# Amplifier.net
KiCad netlist of a schematic drawn in EAGLE
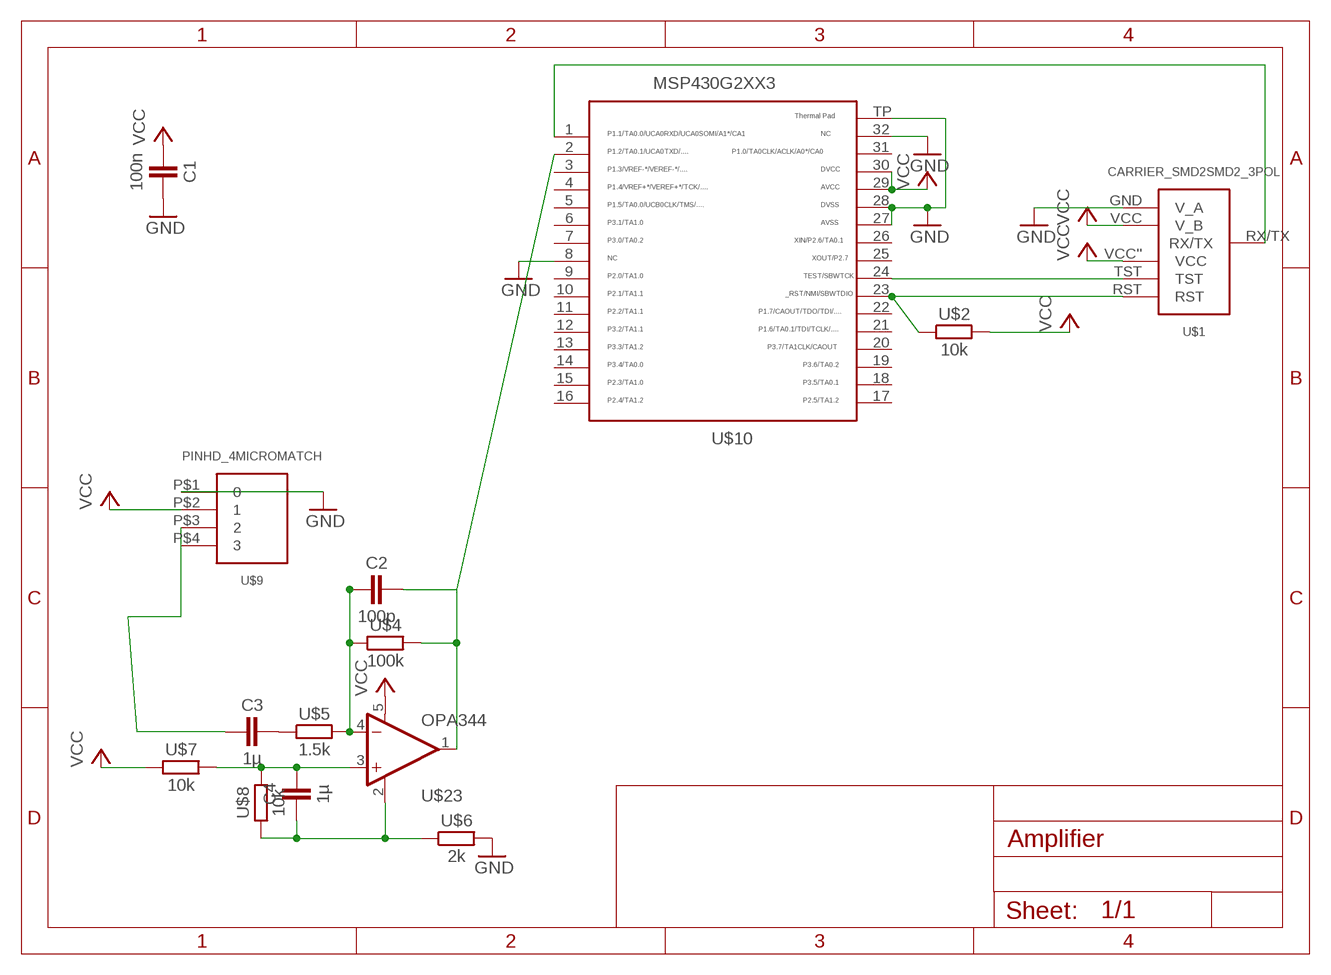
[diagram p0: schematic, sheet 1]

(export (version "E")
  (design (tool "Eeschema 10.0.6"))
  (components
    (comp (ref "C1")
      (value "100n")
      (footprint "eagle-import:603")
      (libsource (lib "eagle-import") (part "CAPACITOR"))
    )
    (comp (ref "C2")
      (value "100p")
      (footprint "eagle-import:603")
      (libsource (lib "eagle-import") (part "CAPACITOR"))
    )
    (comp (ref "C3")
      (value "1µ")
      (footprint "eagle-import:603")
      (libsource (lib "eagle-import") (part "CAPACITOR"))
    )
    (comp (ref "C4")
      (value "1µ")
      (footprint "eagle-import:603")
      (libsource (lib "eagle-import") (part "CAPACITOR"))
    )
    (comp (ref "U$1")
      (value "CARRIER_SMD2SMD2_3POL")
      (footprint "eagle-import:CARRIER_SMD2_3POL")
      (libsource (lib "eagle-import") (part "CARRIER_SMD2SMD2_3POL"))
    )
    (comp (ref "U$2")
      (value "10k")
      (footprint "eagle-import:603")
      (libsource (lib "eagle-import") (part "RESISTOR0603"))
    )
    (comp (ref "U$4")
      (value "100k")
      (footprint "eagle-import:603")
      (libsource (lib "eagle-import") (part "RESISTOR0603"))
    )
    (comp (ref "U$5")
      (value "1.5k")
      (footprint "eagle-import:603")
      (libsource (lib "eagle-import") (part "RESISTOR0603"))
    )
    (comp (ref "U$6")
      (value "2k")
      (footprint "eagle-import:603")
      (libsource (lib "eagle-import") (part "RESISTOR0603"))
    )
    (comp (ref "U$7")
      (value "10k")
      (footprint "eagle-import:603")
      (libsource (lib "eagle-import") (part "RESISTOR0603"))
    )
    (comp (ref "U$8")
      (value "10k")
      (footprint "eagle-import:603")
      (libsource (lib "eagle-import") (part "RESISTOR0603"))
    )
    (comp (ref "U$9")
      (value "PINHD_4MICROMATCH")
      (footprint "eagle-import:MICROMATCH4P0L")
      (libsource (lib "eagle-import") (part "PINHD_4MICROMATCH"))
    )
    (comp (ref "U$10")
      (value "MSP430G2553")
      (footprint "eagle-import:QFN32")
      (libsource (lib "eagle-import") (part "MSP430G2553"))
    )
    (comp (ref "U$23")
      (value "OPA344")
      (footprint "eagle-import:SOT23-5")
      (libsource (lib "eagle-import") (part "OPA344"))
    )
  )
  (nets
    (net (code "1") (name "GND") (class "Default")
      (node (ref "C1") (pin "2") (pinfunction "2_2") (pintype "passive"))
      (node (ref "U$1") (pin "GND") (pinfunction "V_A_GND") (pintype "bidirectional"))
      (node (ref "U$10") (pin "27") (pinfunction "27_27") (pintype "bidirectional"))
      (node (ref "U$10") (pin "28") (pinfunction "28_28") (pintype "bidirectional"))
      (node (ref "U$10") (pin "32") (pinfunction "32_32") (pintype "bidirectional"))
      (node (ref "U$10") (pin "8") (pinfunction "8_8") (pintype "bidirectional"))
      (node (ref "U$10") (pin "TP") (pinfunction "TP_TP") (pintype "bidirectional"))
      (node (ref "U$6") (pin "2") (pinfunction "2_2") (pintype "passive"))
      (node (ref "U$9") (pin "P$1") (pinfunction "0_P$1") (pintype "bidirectional"))
    )
    (net (code "2") (name "Net-(C3-Pad2)") (class "Default")
      (node (ref "C3") (pin "2") (pinfunction "2_2") (pintype "passive"))
      (node (ref "U$5") (pin "1") (pinfunction "1_1") (pintype "passive"))
    )
    (net (code "3") (name "Net-(U$1-PadRST)") (class "Default")
      (node (ref "U$1") (pin "RST") (pinfunction "RST_RST") (pintype "bidirectional"))
      (node (ref "U$10") (pin "23") (pinfunction "23_23") (pintype "bidirectional"))
      (node (ref "U$2") (pin "1") (pinfunction "1_1") (pintype "passive"))
    )
    (net (code "4") (name "Net-(U$1-PadRX{slash}TX)") (class "Default")
      (node (ref "U$1") (pin "RX/TX") (pinfunction "RX/TX_RX/TX") (pintype "bidirectional"))
      (node (ref "U$10") (pin "1") (pinfunction "1_1") (pintype "bidirectional"))
    )
    (net (code "5") (name "Net-(U$1-PadTST)") (class "Default")
      (node (ref "U$1") (pin "TST") (pinfunction "TST_TST") (pintype "bidirectional"))
      (node (ref "U$10") (pin "24") (pinfunction "24_24") (pintype "bidirectional"))
    )
    (net (code "6") (name "Net-(U$9-2)") (class "Default")
      (node (ref "C3") (pin "1") (pinfunction "1_1") (pintype "passive"))
      (node (ref "U$9") (pin "P$3") (pinfunction "2_P$3") (pintype "bidirectional"))
      (node (ref "U$9") (pin "P$4") (pinfunction "3_P$4") (pintype "bidirectional"))
    )
    (net (code "7") (name "Net-(U$23-+IN)") (class "Default")
      (node (ref "C4") (pin "2") (pinfunction "2_2") (pintype "passive"))
      (node (ref "U$23") (pin "3") (pinfunction "+IN_3") (pintype "input"))
      (node (ref "U$7") (pin "2") (pinfunction "2_2") (pintype "passive"))
      (node (ref "U$8") (pin "2") (pinfunction "2_2") (pintype "passive"))
    )
    (net (code "8") (name "Net-(U$23--IN)") (class "Default")
      (node (ref "C2") (pin "1") (pinfunction "1_1") (pintype "passive"))
      (node (ref "U$23") (pin "4") (pinfunction "-IN_4") (pintype "input"))
      (node (ref "U$4") (pin "1") (pinfunction "1_1") (pintype "passive"))
      (node (ref "U$5") (pin "2") (pinfunction "2_2") (pintype "passive"))
    )
    (net (code "9") (name "Net-(U$23-OUT)") (class "Default")
      (node (ref "C2") (pin "2") (pinfunction "2_2") (pintype "passive"))
      (node (ref "U$10") (pin "2") (pinfunction "2_2") (pintype "bidirectional"))
      (node (ref "U$23") (pin "1") (pinfunction "OUT_1") (pintype "output"))
      (node (ref "U$4") (pin "2") (pinfunction "2_2") (pintype "passive"))
    )
    (net (code "10") (name "Net-(U$23-V-)") (class "Default")
      (node (ref "C4") (pin "1") (pinfunction "1_1") (pintype "passive"))
      (node (ref "U$23") (pin "2") (pinfunction "V-_2") (pintype "power_in"))
      (node (ref "U$6") (pin "1") (pinfunction "1_1") (pintype "passive"))
      (node (ref "U$8") (pin "1") (pinfunction "1_1") (pintype "passive"))
    )
    (net (code "11") (name "VCC") (class "Default")
      (node (ref "C1") (pin "1") (pinfunction "1_1") (pintype "passive"))
      (node (ref "U$1") (pin "VCC") (pinfunction "V_B_VCC") (pintype "bidirectional"))
      (node (ref "U$1") (pin "VCC''") (pinfunction "VCC_VCC''") (pintype "bidirectional"))
      (node (ref "U$10") (pin "29") (pinfunction "29_29") (pintype "bidirectional"))
      (node (ref "U$10") (pin "30") (pinfunction "30_30") (pintype "bidirectional"))
      (node (ref "U$2") (pin "2") (pinfunction "2_2") (pintype "passive"))
      (node (ref "U$23") (pin "5") (pinfunction "V+_5") (pintype "power_in"))
      (node (ref "U$7") (pin "1") (pinfunction "1_1") (pintype "passive"))
      (node (ref "U$9") (pin "P$2") (pinfunction "1_P$2") (pintype "bidirectional"))
    )
    (net (code "12") (name "unconnected-(U$10-Pad3)") (class "Default")
      (node (ref "U$10") (pin "3") (pinfunction "3_3") (pintype "bidirectional"))
    )
    (net (code "13") (name "unconnected-(U$10-Pad4)") (class "Default")
      (node (ref "U$10") (pin "4") (pinfunction "4_4") (pintype "bidirectional"))
    )
    (net (code "14") (name "unconnected-(U$10-Pad5)") (class "Default")
      (node (ref "U$10") (pin "5") (pinfunction "5_5") (pintype "bidirectional"))
    )
    (net (code "15") (name "unconnected-(U$10-Pad6)") (class "Default")
      (node (ref "U$10") (pin "6") (pinfunction "6_6") (pintype "bidirectional"))
    )
    (net (code "16") (name "unconnected-(U$10-Pad7)") (class "Default")
      (node (ref "U$10") (pin "7") (pinfunction "7_7") (pintype "bidirectional"))
    )
    (net (code "17") (name "unconnected-(U$10-Pad9)") (class "Default")
      (node (ref "U$10") (pin "9") (pinfunction "9_9") (pintype "bidirectional"))
    )
    (net (code "18") (name "unconnected-(U$10-Pad10)") (class "Default")
      (node (ref "U$10") (pin "10") (pinfunction "10_10") (pintype "bidirectional"))
    )
    (net (code "19") (name "unconnected-(U$10-Pad11)") (class "Default")
      (node (ref "U$10") (pin "11") (pinfunction "11_11") (pintype "bidirectional"))
    )
    (net (code "20") (name "unconnected-(U$10-Pad12)") (class "Default")
      (node (ref "U$10") (pin "12") (pinfunction "12_12") (pintype "bidirectional"))
    )
    (net (code "21") (name "unconnected-(U$10-Pad13)") (class "Default")
      (node (ref "U$10") (pin "13") (pinfunction "13_13") (pintype "bidirectional"))
    )
    (net (code "22") (name "unconnected-(U$10-Pad14)") (class "Default")
      (node (ref "U$10") (pin "14") (pinfunction "14_14") (pintype "bidirectional"))
    )
    (net (code "23") (name "unconnected-(U$10-Pad15)") (class "Default")
      (node (ref "U$10") (pin "15") (pinfunction "15_15") (pintype "bidirectional"))
    )
    (net (code "24") (name "unconnected-(U$10-Pad16)") (class "Default")
      (node (ref "U$10") (pin "16") (pinfunction "16_16") (pintype "bidirectional"))
    )
    (net (code "25") (name "unconnected-(U$10-Pad17)") (class "Default")
      (node (ref "U$10") (pin "17") (pinfunction "17_17") (pintype "bidirectional"))
    )
    (net (code "26") (name "unconnected-(U$10-Pad18)") (class "Default")
      (node (ref "U$10") (pin "18") (pinfunction "18_18") (pintype "bidirectional"))
    )
    (net (code "27") (name "unconnected-(U$10-Pad19)") (class "Default")
      (node (ref "U$10") (pin "19") (pinfunction "19_19") (pintype "bidirectional"))
    )
    (net (code "28") (name "unconnected-(U$10-Pad20)") (class "Default")
      (node (ref "U$10") (pin "20") (pinfunction "20_20") (pintype "bidirectional"))
    )
    (net (code "29") (name "unconnected-(U$10-Pad21)") (class "Default")
      (node (ref "U$10") (pin "21") (pinfunction "21_21") (pintype "bidirectional"))
    )
    (net (code "30") (name "unconnected-(U$10-Pad22)") (class "Default")
      (node (ref "U$10") (pin "22") (pinfunction "22_22") (pintype "bidirectional"))
    )
    (net (code "31") (name "unconnected-(U$10-Pad25)") (class "Default")
      (node (ref "U$10") (pin "25") (pinfunction "25_25") (pintype "bidirectional"))
    )
    (net (code "32") (name "unconnected-(U$10-Pad26)") (class "Default")
      (node (ref "U$10") (pin "26") (pinfunction "26_26") (pintype "bidirectional"))
    )
    (net (code "33") (name "unconnected-(U$10-Pad31)") (class "Default")
      (node (ref "U$10") (pin "31") (pinfunction "31_31") (pintype "bidirectional"))
    )
  )
)
